# I2C_EXPANDER.net
KiCad netlist of a schematic drawn in Altium Designer
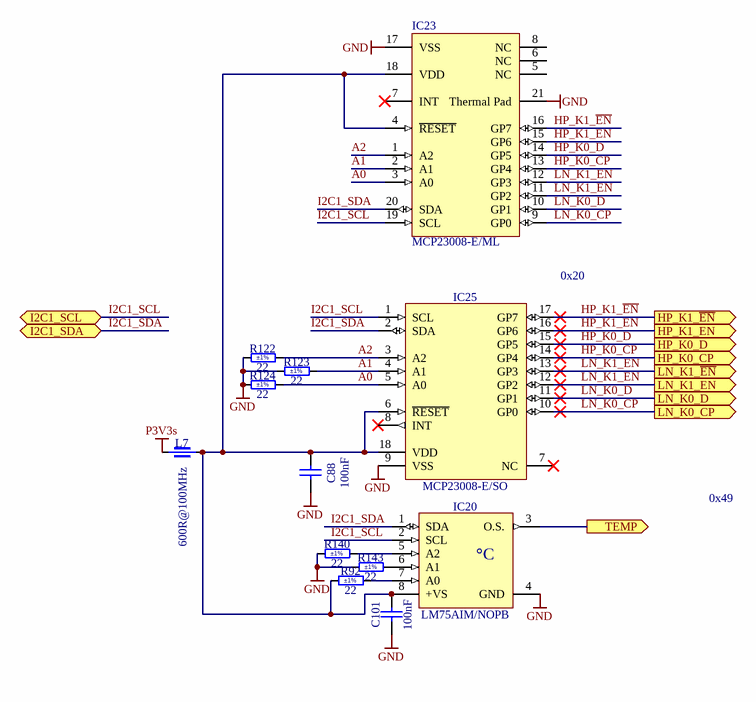
[diagram p0: I2C_EXPANDER.SchDoc]

(export (version "E")
  (design (tool "Eeschema 10.0.6"))
  (components
    (comp (ref "C88")
      (value "100nF")
      (footprint "CAPC1608X87N")
      (description "Non-polarised capacitor")
      (fields
        (field (name "PART NUMBER") "CC0603_100NF_50V_10%_X7R")
        (field (name "VOLTAGE") "50V")
        (field (name "AUTHOR") "CERN DEM JLC")
      )
      (libsource (lib "Capacitors") (part "Capacitor - non polarized"))
    )
    (comp (ref "C101")
      (value "100nF")
      (footprint "CAPC1608X87N")
      (description "Non-polarised capacitor")
      (fields
        (field (name "PART NUMBER") "CC0603_100NF_50V_10%_X7R")
        (field (name "VOLTAGE") "50V")
        (field (name "AUTHOR") "CERN DEM JLC")
      )
      (libsource (lib "Capacitors") (part "Capacitor - non polarized"))
    )
    (comp (ref "IC20")
      (value "LM75AIM/NOPB")
      (footprint "SOIC127P600X175-8N")
      (description "Digital Temperature Sensor and Thermal Watchdog with Two-Wire Interface")
      (fields (field (name "MANUFACTURER") "TEXAS INSTRUMENTS") (field (name "AUTHOR") "CERN DEM JLC"))
      (libsource (lib "ICs And Semiconductors") (part "LM75"))
    )
    (comp (ref "IC23")
      (value "MCP23008-E/ML")
      (footprint "QFN-ML20_M")
      (description "8-Bit I/O Expander with Serial Interface, 20-Pin QFN, Extended Temperature")
      (libsource (lib "Altium Content Vault") (part "PR-BUSIC-MCP23008-21"))
    )
    (comp (ref "IC25")
      (value "MCP23008-E/SO")
      (footprint "SOIC127P1030X265-18N")
      (description "8-Bit I/O Expander with Serial Interface")
      (fields (field (name "MANUFACTURER") "MICROCHIP TECHNOLOGY") (field (name "AUTHOR") "CERN DEM JLC"))
      (libsource (lib "ICs And Semiconductors") (part "MCP23008-E/SO"))
    )
    (comp (ref "L7")
      (value "600R@100MHz")
      (footprint "INDC1608X95N")
      (fields
        (field (name "PART NUMBER") "IND0603_MURATA_BLM18AG601SN1")
        (field (name "POWER") "500mA")
        (field (name "TOLERANCE") "±25%")
        (field (name "AUTHOR") "CERN DEM MR")
      )
      (libsource (lib "Inductors & Transformers") (part "Ferrite Bead"))
    )
    (comp (ref "R92")
      (value "22")
      (footprint "RESC1608X55N")
      (description "Resistor - 1%")
      (fields
        (field (name "TOLERANCE") "±1%")
        (field (name "PART NUMBER") "R0603_22R_1%_0.1W_100PPM")
        (field (name "POWER") "0.1W")
        (field (name "AUTHOR") "CERN DEM JLC")
      )
      (libsource (lib "Resistors") (part "Resistor - 1%"))
    )
    (comp (ref "R122")
      (value "22")
      (footprint "RESC1608X55N")
      (description "Resistor - 1%")
      (fields
        (field (name "TOLERANCE") "±1%")
        (field (name "PART NUMBER") "R0603_22R_1%_0.1W_100PPM")
        (field (name "POWER") "0.1W")
        (field (name "AUTHOR") "CERN DEM JLC")
      )
      (libsource (lib "Resistors") (part "Resistor - 1%"))
    )
    (comp (ref "R123")
      (value "22")
      (footprint "RESC1608X55N")
      (description "Resistor - 1%")
      (fields
        (field (name "TOLERANCE") "±1%")
        (field (name "PART NUMBER") "R0603_22R_1%_0.1W_100PPM")
        (field (name "POWER") "0.1W")
        (field (name "AUTHOR") "CERN DEM JLC")
      )
      (libsource (lib "Resistors") (part "Resistor - 1%"))
    )
    (comp (ref "R124")
      (value "22")
      (footprint "RESC1608X55N")
      (description "Resistor - 1%")
      (fields
        (field (name "TOLERANCE") "±1%")
        (field (name "PART NUMBER") "R0603_22R_1%_0.1W_100PPM")
        (field (name "POWER") "0.1W")
        (field (name "AUTHOR") "CERN DEM JLC")
      )
      (libsource (lib "Resistors") (part "Resistor - 1%"))
    )
    (comp (ref "R140")
      (value "22")
      (footprint "RESC1608X55N")
      (description "Resistor - 1%")
      (fields
        (field (name "TOLERANCE") "±1%")
        (field (name "PART NUMBER") "R0603_22R_1%_0.1W_100PPM")
        (field (name "POWER") "0.1W")
        (field (name "AUTHOR") "CERN DEM JLC")
      )
      (libsource (lib "Resistors") (part "Resistor - 1%"))
    )
    (comp (ref "R143")
      (value "22")
      (footprint "RESC1608X55N")
      (description "Resistor - 1%")
      (fields
        (field (name "TOLERANCE") "±1%")
        (field (name "PART NUMBER") "R0603_22R_1%_0.1W_100PPM")
        (field (name "POWER") "0.1W")
        (field (name "AUTHOR") "CERN DEM JLC")
      )
      (libsource (lib "Resistors") (part "Resistor - 1%"))
    )
  )
  (nets
    (net (code "1") (name "/A0") (class "Default")
      (node (ref "IC23") (pin "3") (pinfunction "A0_3") (pintype "input"))
      (node (ref "IC25") (pin "5") (pinfunction "A0_5") (pintype "input"))
      (node (ref "R124") (pin "2") (pinfunction "2_2") (pintype "passive"))
    )
    (net (code "2") (name "/A1") (class "Default")
      (node (ref "IC23") (pin "2") (pinfunction "A1_2") (pintype "input"))
      (node (ref "IC25") (pin "4") (pinfunction "A1_4") (pintype "input"))
      (node (ref "R123") (pin "2") (pinfunction "2_2") (pintype "passive"))
    )
    (net (code "3") (name "/A2") (class "Default")
      (node (ref "IC23") (pin "1") (pinfunction "A2_1") (pintype "input"))
      (node (ref "IC25") (pin "3") (pinfunction "A2_3") (pintype "input"))
      (node (ref "R122") (pin "2") (pinfunction "2_2") (pintype "passive"))
    )
    (net (code "4") (name "/HP_K0_CP") (class "Default")
      (node (ref "IC23") (pin "13") (pinfunction "GP4_13") (pintype "bidirectional"))
      (node (ref "IC25") (pin "14") (pinfunction "GP4_14") (pintype "bidirectional"))
    )
    (net (code "5") (name "/HP_K0_D") (class "Default")
      (node (ref "IC23") (pin "14") (pinfunction "GP5_14") (pintype "bidirectional"))
      (node (ref "IC25") (pin "15") (pinfunction "GP5_15") (pintype "bidirectional"))
    )
    (net (code "6") (name "/HP_K1_EN") (class "Default")
      (node (ref "IC23") (pin "15") (pinfunction "GP6_15") (pintype "bidirectional"))
      (node (ref "IC25") (pin "16") (pinfunction "GP6_16") (pintype "bidirectional"))
    )
    (net (code "7") (name "/HP_K1_~{EN}") (class "Default")
      (node (ref "IC23") (pin "16") (pinfunction "GP7_16") (pintype "bidirectional"))
      (node (ref "IC25") (pin "17") (pinfunction "GP7_17") (pintype "bidirectional"))
    )
    (net (code "8") (name "/I2C1_SCL") (class "Default")
      (node (ref "IC20") (pin "2") (pinfunction "SCL_2") (pintype "input"))
      (node (ref "IC23") (pin "19") (pinfunction "SCL_19") (pintype "input"))
      (node (ref "IC25") (pin "1") (pinfunction "SCL_1") (pintype "input"))
    )
    (net (code "9") (name "/I2C1_SDA") (class "Default")
      (node (ref "IC20") (pin "1") (pinfunction "SDA_1") (pintype "bidirectional"))
      (node (ref "IC23") (pin "20") (pinfunction "SDA_20") (pintype "bidirectional"))
      (node (ref "IC25") (pin "2") (pinfunction "SDA_2") (pintype "bidirectional"))
    )
    (net (code "10") (name "/LN_K0_CP") (class "Default")
      (node (ref "IC23") (pin "9") (pinfunction "GP0_9") (pintype "bidirectional"))
      (node (ref "IC25") (pin "10") (pinfunction "GP0_10") (pintype "bidirectional"))
    )
    (net (code "11") (name "/LN_K0_D") (class "Default")
      (node (ref "IC23") (pin "10") (pinfunction "GP1_10") (pintype "bidirectional"))
      (node (ref "IC25") (pin "11") (pinfunction "GP1_11") (pintype "bidirectional"))
    )
    (net (code "12") (name "/LN_K1_EN") (class "Default")
      (node (ref "IC23") (pin "11") (pinfunction "GP2_11") (pintype "bidirectional"))
      (node (ref "IC25") (pin "12") (pinfunction "GP2_12") (pintype "bidirectional"))
    )
    (net (code "13") (name "/LN_K1_~{EN}") (class "Default")
      (node (ref "IC23") (pin "12") (pinfunction "GP3_12") (pintype "bidirectional"))
      (node (ref "IC25") (pin "13") (pinfunction "GP3_13") (pintype "bidirectional"))
    )
    (net (code "14") (name "/TEMP") (class "Default")
      (node (ref "IC20") (pin "3") (pinfunction "O.S._3") (pintype "output"))
    )
    (net (code "15") (name "GND") (class "Default")
      (node (ref "C101") (pin "1") (pinfunction "1_1") (pintype "passive"))
      (node (ref "C88") (pin "1") (pinfunction "1_1") (pintype "passive"))
      (node (ref "IC20") (pin "4") (pinfunction "GND_4") (pintype "power_in"))
      (node (ref "IC23") (pin "17") (pinfunction "VSS_17") (pintype "power_in"))
      (node (ref "IC23") (pin "21") (pinfunction "Thermal_Pad_21") (pintype "passive"))
      (node (ref "IC25") (pin "9") (pinfunction "VSS_9") (pintype "power_in"))
      (node (ref "R122") (pin "1") (pinfunction "1_1") (pintype "passive"))
      (node (ref "R123") (pin "1") (pinfunction "1_1") (pintype "passive"))
      (node (ref "R124") (pin "1") (pinfunction "1_1") (pintype "passive"))
      (node (ref "R140") (pin "1") (pinfunction "1_1") (pintype "passive"))
      (node (ref "R143") (pin "1") (pinfunction "1_1") (pintype "passive"))
    )
    (net (code "16") (name "Net-(IC20-+VS)") (class "Default")
      (node (ref "C101") (pin "2") (pinfunction "2_2") (pintype "passive"))
      (node (ref "C88") (pin "2") (pinfunction "2_2") (pintype "passive"))
      (node (ref "IC20") (pin "8") (pinfunction "+VS_8") (pintype "power_in"))
      (node (ref "IC23") (pin "18") (pinfunction "VDD_18") (pintype "power_in"))
      (node (ref "IC23") (pin "4") (pinfunction "~{RESET}_4") (pintype "input"))
      (node (ref "IC25") (pin "18") (pinfunction "VDD_18") (pintype "power_in"))
      (node (ref "IC25") (pin "6") (pinfunction "~{RESET}_6") (pintype "input"))
      (node (ref "L7") (pin "2") (pinfunction "2_2") (pintype "passive"))
      (node (ref "R92") (pin "1") (pinfunction "1_1") (pintype "passive"))
    )
    (net (code "17") (name "Net-(IC20-A0)") (class "Default")
      (node (ref "IC20") (pin "7") (pinfunction "A0_7") (pintype "input"))
      (node (ref "R92") (pin "2") (pinfunction "2_2") (pintype "passive"))
    )
    (net (code "18") (name "Net-(IC20-A1)") (class "Default")
      (node (ref "IC20") (pin "6") (pinfunction "A1_6") (pintype "input"))
      (node (ref "R143") (pin "2") (pinfunction "2_2") (pintype "passive"))
    )
    (net (code "19") (name "Net-(IC20-A2)") (class "Default")
      (node (ref "IC20") (pin "5") (pinfunction "A2_5") (pintype "input"))
      (node (ref "R140") (pin "2") (pinfunction "2_2") (pintype "passive"))
    )
    (net (code "20") (name "P3V3s") (class "Default")
      (node (ref "L7") (pin "1") (pinfunction "1_1") (pintype "passive"))
    )
    (net (code "21") (name "unconnected-(IC23-INT-Pad7)") (class "Default")
      (node (ref "IC23") (pin "7") (pinfunction "INT_7") (pintype "open_collector+no_connect"))
    )
    (net (code "22") (name "unconnected-(IC23-NC-Pad5)") (class "Default")
      (node (ref "IC23") (pin "5") (pinfunction "NC_5") (pintype "passive"))
    )
    (net (code "23") (name "unconnected-(IC23-NC-Pad6)") (class "Default")
      (node (ref "IC23") (pin "6") (pinfunction "NC_6") (pintype "passive"))
    )
    (net (code "24") (name "unconnected-(IC23-NC-Pad8)") (class "Default")
      (node (ref "IC23") (pin "8") (pinfunction "NC_8") (pintype "passive"))
    )
    (net (code "25") (name "unconnected-(IC25-INT-Pad8)") (class "Default")
      (node (ref "IC25") (pin "8") (pinfunction "INT_8") (pintype "output+no_connect"))
    )
    (net (code "26") (name "unconnected-(IC25-NC-Pad7)") (class "Default")
      (node (ref "IC25") (pin "7") (pinfunction "NC_7") (pintype "passive+no_connect"))
    )
  )
)
